# PCB.net
KiCad netlist of a schematic drawn in EAGLE
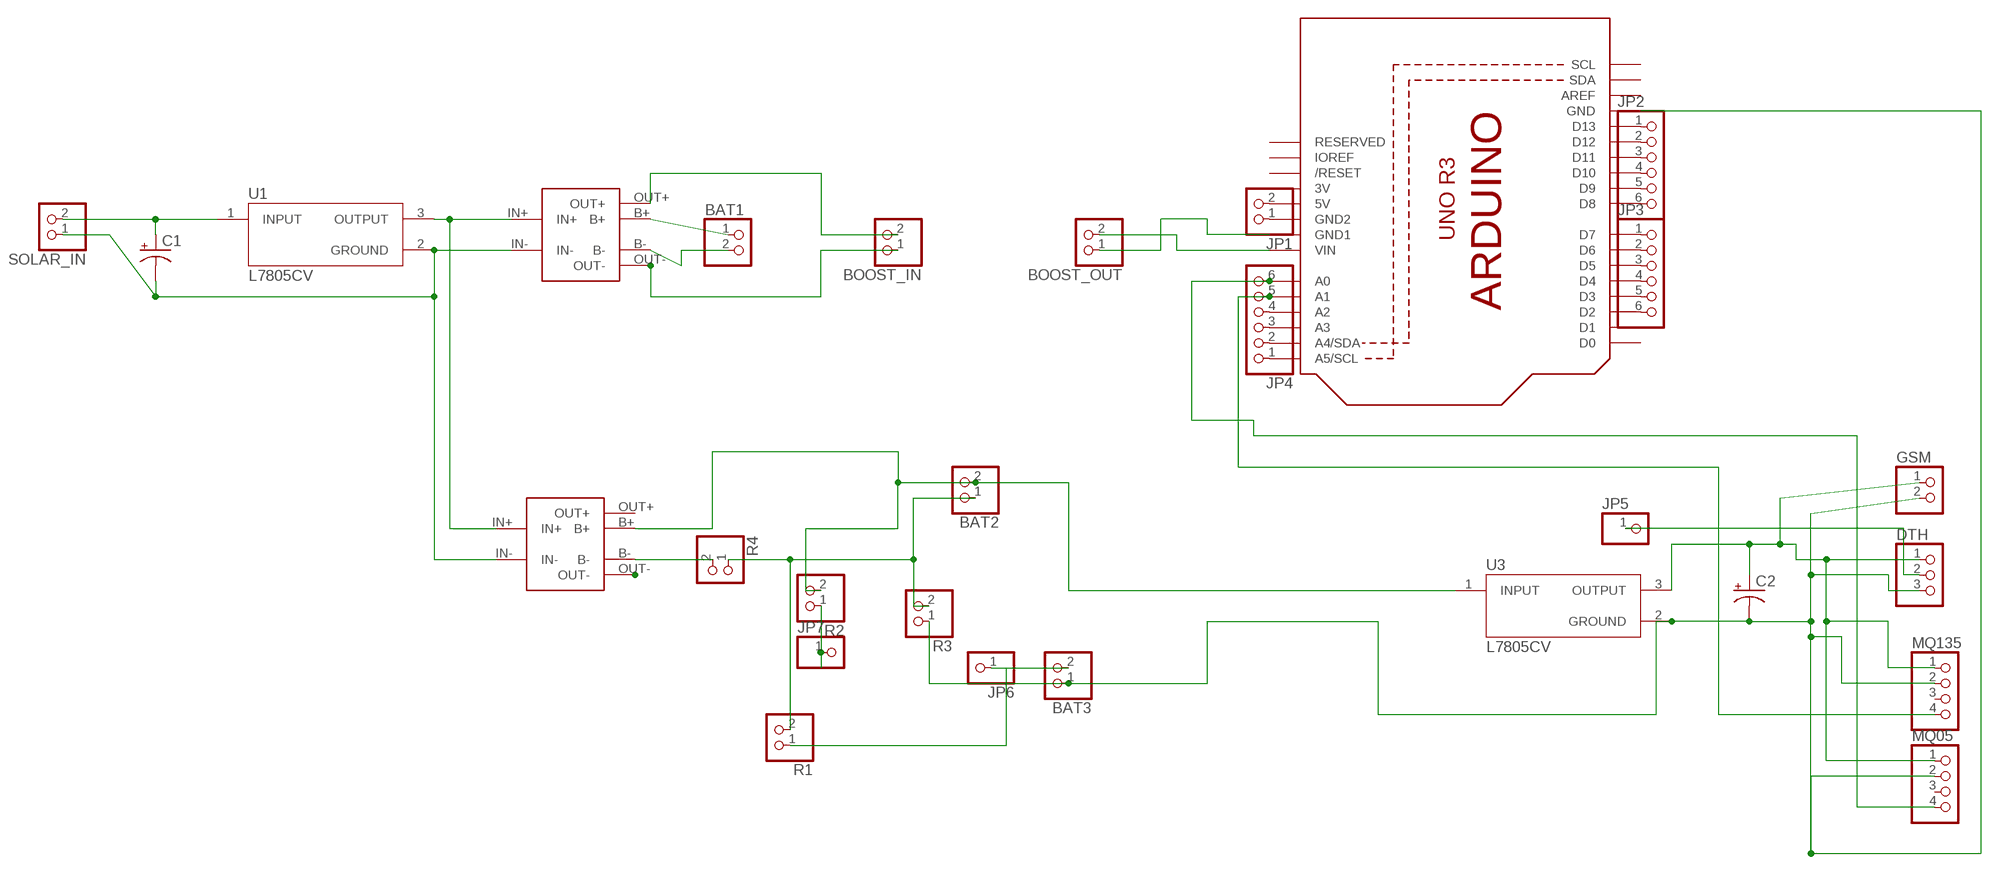
[diagram p0: schematic, sheet 1]

(export (version "E")
  (design (tool "Eeschema 10.0.6"))
  (components
    (comp (ref "BAT1")
      (value "PINHD-1X2")
      (footprint "eagle-import:1X02")
      (libsource (lib "eagle-import") (part "PINHD-1X2"))
    )
    (comp (ref "BAT2")
      (value "PINHD-1X2")
      (footprint "eagle-import:1X02")
      (libsource (lib "eagle-import") (part "PINHD-1X2"))
    )
    (comp (ref "BAT3")
      (value "PINHD-1X2")
      (footprint "eagle-import:1X02")
      (libsource (lib "eagle-import") (part "PINHD-1X2"))
    )
    (comp (ref "BOOST_IN")
      (value "PINHD-1X2")
      (footprint "eagle-import:1X02")
      (libsource (lib "eagle-import") (part "PINHD-1X2"))
    )
    (comp (ref "BOOST_OUT")
      (value "PINHD-1X2")
      (footprint "eagle-import:1X02")
      (libsource (lib "eagle-import") (part "PINHD-1X2"))
    )
    (comp (ref "C1")
      (value "C-POL-US_RADIAL-11MM-DIA")
      (footprint "eagle-import:CAPPRD508W65D1000H1100B")
      (libsource (lib "eagle-import") (part "C-POL-USRADIAL-11MM-DIA_"))
    )
    (comp (ref "C2")
      (value "C-POL-US_RADIAL-11MM-DIA")
      (footprint "eagle-import:CAPPRD508W65D1000H1100B")
      (libsource (lib "eagle-import") (part "C-POL-USRADIAL-11MM-DIA_"))
    )
    (comp (ref "DTH")
      (value "PINHD-1X3")
      (footprint "eagle-import:1X03")
      (libsource (lib "eagle-import") (part "PINHD-1X3"))
    )
    (comp (ref "GSM")
      (value "PINHD-1X2")
      (footprint "eagle-import:1X02")
      (libsource (lib "eagle-import") (part "PINHD-1X2"))
    )
    (comp (ref "JP1")
      (value "PINHD-1X2")
      (footprint "eagle-import:1X02")
      (libsource (lib "eagle-import") (part "pinhead_325_PINHD-1X2"))
    )
    (comp (ref "JP2")
      (value "PINHD-1X6")
      (footprint "eagle-import:1X06")
      (libsource (lib "eagle-import") (part "PINHD-1X6"))
    )
    (comp (ref "JP3")
      (value "PINHD-1X6")
      (footprint "eagle-import:1X06")
      (libsource (lib "eagle-import") (part "PINHD-1X6"))
    )
    (comp (ref "JP4")
      (value "PINHD-1X6")
      (footprint "eagle-import:1X06")
      (libsource (lib "eagle-import") (part "PINHD-1X6"))
    )
    (comp (ref "JP5")
      (value "PINHD-1X1")
      (footprint "eagle-import:1X01")
      (libsource (lib "eagle-import") (part "PINHD-1X1"))
    )
    (comp (ref "JP6")
      (value "PINHD-1X1")
      (footprint "eagle-import:1X01")
      (libsource (lib "eagle-import") (part "PINHD-1X1"))
    )
    (comp (ref "JP7")
      (value "PINHD-1X1")
      (footprint "eagle-import:1X01")
      (libsource (lib "eagle-import") (part "PINHD-1X1"))
    )
    (comp (ref "MQ05")
      (value "PINHD-1X4")
      (footprint "eagle-import:1X04")
      (libsource (lib "eagle-import") (part "PINHD-1X4"))
    )
    (comp (ref "MQ135")
      (value "PINHD-1X4")
      (footprint "eagle-import:1X04")
      (libsource (lib "eagle-import") (part "PINHD-1X4"))
    )
    (comp (ref "R1")
      (value "PINHD-1X2")
      (footprint "eagle-import:1X02")
      (libsource (lib "eagle-import") (part "PINHD-1X2"))
    )
    (comp (ref "R2")
      (value "PINHD-1X2")
      (footprint "eagle-import:1X02")
      (libsource (lib "eagle-import") (part "PINHD-1X2"))
    )
    (comp (ref "R3")
      (value "PINHD-1X2")
      (footprint "eagle-import:1X02")
      (libsource (lib "eagle-import") (part "PINHD-1X2"))
    )
    (comp (ref "R4")
      (value "PINHD-1X2")
      (footprint "eagle-import:1X02")
      (libsource (lib "eagle-import") (part "PINHD-1X2"))
    )
    (comp (ref "SOLAR_IN")
      (value "PINHD-1X2")
      (footprint "eagle-import:1X02")
      (libsource (lib "eagle-import") (part "PINHD-1X2"))
    )
    (comp (ref "U$3")
      (value "TP4056-PTH")
      (footprint "eagle-import:TP4056-PTH")
      (libsource (lib "eagle-import") (part "TP4056-PTH"))
    )
    (comp (ref "U$5")
      (value "TP4056-PTH")
      (footprint "eagle-import:TP4056-PTH")
      (libsource (lib "eagle-import") (part "TP4056-PTH"))
    )
    (comp (ref "U1")
      (value "L7805CV")
      (footprint "eagle-import:TO255P1040X460X1968-3")
      (fields (field (name "MF") "STMicroelectronics"))
      (libsource (lib "eagle-import") (part "L7805CV"))
    )
    (comp (ref "U2")
      (value "ARDUINOR3-DIMENSION")
      (footprint "eagle-import:ARDUINOR3")
      (libsource (lib "eagle-import") (part "ARDUINOR3-DIMENSION"))
    )
    (comp (ref "U3")
      (value "L7805CV")
      (footprint "eagle-import:TO255P1040X460X1968-3")
      (fields (field (name "MF") "STMicroelectronics"))
      (libsource (lib "eagle-import") (part "L7805CV"))
    )
  )
  (nets
    (net (code "1") (name "/3V") (class "Default")
      (node (ref "U2") (pin "3V") (pinfunction "3V_3V") (pintype "power_in"))
    )
    (net (code "2") (name "Net-(BAT1-Pad1)") (class "Default")
      (node (ref "BAT1") (pin "1") (pinfunction "1_1") (pintype "passive"))
      (node (ref "U$3") (pin "B+") (pinfunction "B+_B+") (pintype "bidirectional"))
    )
    (net (code "3") (name "Net-(BAT1-Pad2)") (class "Default")
      (node (ref "BAT1") (pin "2") (pinfunction "2_2") (pintype "passive"))
      (node (ref "U$3") (pin "B-") (pinfunction "B-_B-") (pintype "bidirectional"))
    )
    (net (code "4") (name "Net-(BAT2-Pad1)") (class "Default")
      (node (ref "BAT2") (pin "1") (pinfunction "1_1") (pintype "passive"))
      (node (ref "R1") (pin "2") (pinfunction "2_2") (pintype "passive"))
      (node (ref "R3") (pin "2") (pinfunction "2_2") (pintype "passive"))
      (node (ref "R4") (pin "1") (pinfunction "1_1") (pintype "passive"))
    )
    (net (code "5") (name "Net-(BAT3-Pad2)") (class "Default")
      (node (ref "BAT3") (pin "2") (pinfunction "2_2") (pintype "passive"))
      (node (ref "JP6") (pin "1") (pinfunction "1_1") (pintype "passive"))
    )
    (net (code "6") (name "Net-(BOOST_IN-Pad1)") (class "Default")
      (node (ref "BOOST_IN") (pin "1") (pinfunction "1_1") (pintype "passive"))
      (node (ref "U$3") (pin "OUT-") (pinfunction "OUT-_OUT-") (pintype "bidirectional"))
    )
    (net (code "7") (name "Net-(BOOST_IN-Pad2)") (class "Default")
      (node (ref "BOOST_IN") (pin "2") (pinfunction "2_2") (pintype "passive"))
      (node (ref "U$3") (pin "OUT+") (pinfunction "OUT+_OUT+") (pintype "bidirectional"))
    )
    (net (code "8") (name "Net-(BOOST_OUT-Pad1)") (class "Default")
      (node (ref "BOOST_OUT") (pin "1") (pinfunction "1_1") (pintype "passive"))
      (node (ref "U2") (pin "GND1") (pinfunction "GND1_GND1") (pintype "power_in"))
    )
    (net (code "9") (name "Net-(BOOST_OUT-Pad2)") (class "Default")
      (node (ref "BOOST_OUT") (pin "2") (pinfunction "2_2") (pintype "passive"))
      (node (ref "U2") (pin "VIN") (pinfunction "VIN_VIN") (pintype "power_in"))
    )
    (net (code "10") (name "Net-(C1-+)") (class "Default")
      (node (ref "C1") (pin "1") (pinfunction "+_1") (pintype "passive"))
      (node (ref "SOLAR_IN") (pin "2") (pinfunction "2_2") (pintype "passive"))
      (node (ref "U1") (pin "1") (pinfunction "INPUT_1") (pintype "input"))
    )
    (net (code "11") (name "Net-(C1--)") (class "Default")
      (node (ref "C1") (pin "2") (pinfunction "-_2") (pintype "passive"))
      (node (ref "SOLAR_IN") (pin "1") (pinfunction "1_1") (pintype "passive"))
      (node (ref "U$3") (pin "IN-") (pinfunction "IN-_IN-") (pintype "bidirectional"))
      (node (ref "U$5") (pin "IN-") (pinfunction "IN-_IN-") (pintype "bidirectional"))
      (node (ref "U1") (pin "2") (pinfunction "GROUND_2") (pintype "power_in"))
    )
    (net (code "12") (name "Net-(C2-+)") (class "Default")
      (node (ref "C2") (pin "1") (pinfunction "+_1") (pintype "passive"))
      (node (ref "DTH") (pin "1") (pinfunction "1_1") (pintype "passive"))
      (node (ref "GSM") (pin "1") (pinfunction "1_1") (pintype "passive"))
      (node (ref "MQ05") (pin "1") (pinfunction "1_1") (pintype "passive"))
      (node (ref "MQ135") (pin "1") (pinfunction "1_1") (pintype "passive"))
      (node (ref "U3") (pin "3") (pinfunction "OUTPUT_3") (pintype "output"))
    )
    (net (code "13") (name "Net-(C2--)") (class "Default")
      (node (ref "BAT3") (pin "1") (pinfunction "1_1") (pintype "passive"))
      (node (ref "C2") (pin "2") (pinfunction "-_2") (pintype "passive"))
      (node (ref "DTH") (pin "3") (pinfunction "3_3") (pintype "passive"))
      (node (ref "GSM") (pin "2") (pinfunction "2_2") (pintype "passive"))
      (node (ref "MQ05") (pin "2") (pinfunction "2_2") (pintype "passive"))
      (node (ref "MQ135") (pin "2") (pinfunction "2_2") (pintype "passive"))
      (node (ref "R3") (pin "1") (pinfunction "1_1") (pintype "passive"))
      (node (ref "U2") (pin "GND") (pinfunction "GND_GND") (pintype "power_in"))
      (node (ref "U3") (pin "2") (pinfunction "GROUND_2") (pintype "power_in"))
    )
    (net (code "14") (name "Net-(DTH-Pad2)") (class "Default")
      (node (ref "DTH") (pin "2") (pinfunction "2_2") (pintype "passive"))
      (node (ref "JP5") (pin "1") (pinfunction "1_1") (pintype "passive"))
    )
    (net (code "15") (name "Net-(JP1-Pad1)") (class "Default")
      (node (ref "JP1") (pin "1") (pinfunction "1_1") (pintype "passive"))
      (node (ref "U2") (pin "GND2") (pinfunction "GND2_GND2") (pintype "power_in"))
    )
    (net (code "16") (name "Net-(JP1-Pad2)") (class "Default")
      (node (ref "JP1") (pin "2") (pinfunction "2_2") (pintype "passive"))
      (node (ref "U2") (pin "5V") (pinfunction "5V_5V") (pintype "power_in"))
    )
    (net (code "17") (name "Net-(JP2-Pad1)") (class "Default")
      (node (ref "JP2") (pin "1") (pinfunction "1_1") (pintype "passive"))
      (node (ref "U2") (pin "D13") (pinfunction "D13_D13") (pintype "bidirectional"))
    )
    (net (code "18") (name "Net-(JP2-Pad2)") (class "Default")
      (node (ref "JP2") (pin "2") (pinfunction "2_2") (pintype "passive"))
      (node (ref "U2") (pin "D12") (pinfunction "D12_D12") (pintype "bidirectional"))
    )
    (net (code "19") (name "Net-(JP2-Pad3)") (class "Default")
      (node (ref "JP2") (pin "3") (pinfunction "3_3") (pintype "passive"))
      (node (ref "U2") (pin "D11") (pinfunction "D11_D11") (pintype "bidirectional"))
    )
    (net (code "20") (name "Net-(JP2-Pad4)") (class "Default")
      (node (ref "JP2") (pin "4") (pinfunction "4_4") (pintype "passive"))
      (node (ref "U2") (pin "D10") (pinfunction "D10_D10") (pintype "bidirectional"))
    )
    (net (code "21") (name "Net-(JP2-Pad5)") (class "Default")
      (node (ref "JP2") (pin "5") (pinfunction "5_5") (pintype "passive"))
      (node (ref "U2") (pin "D9") (pinfunction "D9_D9") (pintype "bidirectional"))
    )
    (net (code "22") (name "Net-(JP2-Pad6)") (class "Default")
      (node (ref "JP2") (pin "6") (pinfunction "6_6") (pintype "passive"))
      (node (ref "U2") (pin "D8") (pinfunction "D8_D8") (pintype "bidirectional"))
    )
    (net (code "23") (name "Net-(JP3-Pad1)") (class "Default")
      (node (ref "JP3") (pin "1") (pinfunction "1_1") (pintype "passive"))
      (node (ref "U2") (pin "D7") (pinfunction "D7_D7") (pintype "bidirectional"))
    )
    (net (code "24") (name "Net-(JP3-Pad2)") (class "Default")
      (node (ref "JP3") (pin "2") (pinfunction "2_2") (pintype "passive"))
      (node (ref "U2") (pin "D6") (pinfunction "D6_D6") (pintype "bidirectional"))
    )
    (net (code "25") (name "Net-(JP3-Pad3)") (class "Default")
      (node (ref "JP3") (pin "3") (pinfunction "3_3") (pintype "passive"))
      (node (ref "U2") (pin "D5") (pinfunction "D5_D5") (pintype "bidirectional"))
    )
    (net (code "26") (name "Net-(JP3-Pad4)") (class "Default")
      (node (ref "JP3") (pin "4") (pinfunction "4_4") (pintype "passive"))
      (node (ref "U2") (pin "D4") (pinfunction "D4_D4") (pintype "bidirectional"))
    )
    (net (code "27") (name "Net-(JP3-Pad5)") (class "Default")
      (node (ref "JP3") (pin "5") (pinfunction "5_5") (pintype "passive"))
      (node (ref "U2") (pin "D3") (pinfunction "D3_D3") (pintype "bidirectional"))
    )
    (net (code "28") (name "Net-(JP3-Pad6)") (class "Default")
      (node (ref "JP3") (pin "6") (pinfunction "6_6") (pintype "passive"))
      (node (ref "U2") (pin "D2") (pinfunction "D2_D2") (pintype "bidirectional"))
    )
    (net (code "29") (name "Net-(JP4-Pad3)") (class "Default")
      (node (ref "JP4") (pin "3") (pinfunction "3_3") (pintype "passive"))
      (node (ref "U2") (pin "A3") (pinfunction "A3_A3") (pintype "bidirectional"))
    )
    (net (code "30") (name "Net-(JP4-Pad4)") (class "Default")
      (node (ref "JP4") (pin "4") (pinfunction "4_4") (pintype "passive"))
      (node (ref "U2") (pin "A2") (pinfunction "A2_A2") (pintype "bidirectional"))
    )
    (net (code "31") (name "Net-(JP4-Pad5)") (class "Default")
      (node (ref "JP4") (pin "5") (pinfunction "5_5") (pintype "passive"))
      (node (ref "MQ135") (pin "4") (pinfunction "4_4") (pintype "passive"))
      (node (ref "U2") (pin "A1") (pinfunction "A1_A1") (pintype "bidirectional"))
    )
    (net (code "32") (name "Net-(JP4-Pad6)") (class "Default")
      (node (ref "JP4") (pin "6") (pinfunction "6_6") (pintype "passive"))
      (node (ref "MQ05") (pin "4") (pinfunction "4_4") (pintype "passive"))
      (node (ref "U2") (pin "A0") (pinfunction "A0_A0") (pintype "bidirectional"))
    )
    (net (code "33") (name "Net-(JP7-Pad1)") (class "Default")
      (node (ref "JP7") (pin "1") (pinfunction "1_1") (pintype "passive"))
      (node (ref "R2") (pin "1") (pinfunction "1_1") (pintype "passive"))
    )
    (net (code "34") (name "Net-(R4-Pad2)") (class "Default")
      (node (ref "R4") (pin "2") (pinfunction "2_2") (pintype "passive"))
      (node (ref "U$5") (pin "B-") (pinfunction "B-_B-") (pintype "bidirectional"))
    )
    (net (code "35") (name "Net-(U1-OUTPUT)") (class "Default")
      (node (ref "U$3") (pin "IN+") (pinfunction "IN+_IN+") (pintype "bidirectional"))
      (node (ref "U$5") (pin "IN+") (pinfunction "IN+_IN+") (pintype "bidirectional"))
      (node (ref "U1") (pin "3") (pinfunction "OUTPUT_3") (pintype "output"))
    )
    (net (code "36") (name "Net-(U2-A4{slash}SDA)") (class "Default")
      (node (ref "JP4") (pin "2") (pinfunction "2_2") (pintype "passive"))
      (node (ref "U2") (pin "A4") (pinfunction "A4/SDA_A4") (pintype "bidirectional"))
    )
    (net (code "37") (name "Net-(U2-A5{slash}SCL)") (class "Default")
      (node (ref "JP4") (pin "1") (pinfunction "1_1") (pintype "passive"))
      (node (ref "U2") (pin "A5") (pinfunction "A5/SCL_A5") (pintype "bidirectional"))
    )
    (net (code "38") (name "Net-(U3-INPUT)") (class "Default")
      (node (ref "BAT2") (pin "2") (pinfunction "2_2") (pintype "passive"))
      (node (ref "R2") (pin "2") (pinfunction "2_2") (pintype "passive"))
      (node (ref "U$5") (pin "B+") (pinfunction "B+_B+") (pintype "bidirectional"))
      (node (ref "U3") (pin "1") (pinfunction "INPUT_1") (pintype "input"))
    )
    (net (code "39") (name "unconnected-(MQ05-Pad3)") (class "Default")
      (node (ref "MQ05") (pin "3") (pinfunction "3_3") (pintype "passive"))
    )
    (net (code "40") (name "unconnected-(MQ135-Pad3)") (class "Default")
      (node (ref "MQ135") (pin "3") (pinfunction "3_3") (pintype "passive"))
    )
    (net (code "41") (name "unconnected-(R1-Pad1)") (class "Default")
      (node (ref "R1") (pin "1") (pinfunction "1_1") (pintype "passive"))
    )
    (net (code "42") (name "unconnected-(U$5-PadOUT+)") (class "Default")
      (node (ref "U$5") (pin "OUT+") (pinfunction "OUT+_OUT+") (pintype "bidirectional"))
    )
    (net (code "43") (name "unconnected-(U$5-PadOUT-)") (class "Default")
      (node (ref "U$5") (pin "OUT-") (pinfunction "OUT-_OUT-") (pintype "bidirectional"))
    )
    (net (code "44") (name "unconnected-(U2-PadAREF)") (class "Default")
      (node (ref "U2") (pin "AREF") (pinfunction "AREF_AREF") (pintype "bidirectional"))
    )
    (net (code "45") (name "unconnected-(U2-PadD0)") (class "Default")
      (node (ref "U2") (pin "D0") (pinfunction "D0_D0") (pintype "bidirectional"))
    )
    (net (code "46") (name "unconnected-(U2-PadD1)") (class "Default")
      (node (ref "U2") (pin "D1") (pinfunction "D1_D1") (pintype "bidirectional"))
    )
    (net (code "47") (name "unconnected-(U2-PadIOREF)") (class "Default")
      (node (ref "U2") (pin "IOREF") (pinfunction "IOREF_IOREF") (pintype "output"))
    )
    (net (code "48") (name "unconnected-(U2-PadRESERVED)") (class "Default")
      (node (ref "U2") (pin "RESERVED") (pinfunction "RESERVED_RESERVED") (pintype "no_connect"))
    )
    (net (code "49") (name "unconnected-(U2-PadSCL)") (class "Default")
      (node (ref "U2") (pin "SCL") (pinfunction "SCL_SCL") (pintype "bidirectional"))
    )
    (net (code "50") (name "unconnected-(U2-PadSDA)") (class "Default")
      (node (ref "U2") (pin "SDA") (pinfunction "SDA_SDA") (pintype "bidirectional"))
    )
    (net (code "51") (name "unconnected-(U2-{slash}RESET-PadRESET)") (class "Default")
      (node (ref "U2") (pin "RESET") (pinfunction "/RESET_RESET") (pintype "bidirectional"))
    )
  )
)
